# TIDA-010954-FullBridge.net
KiCad netlist of a schematic drawn in Altium Designer
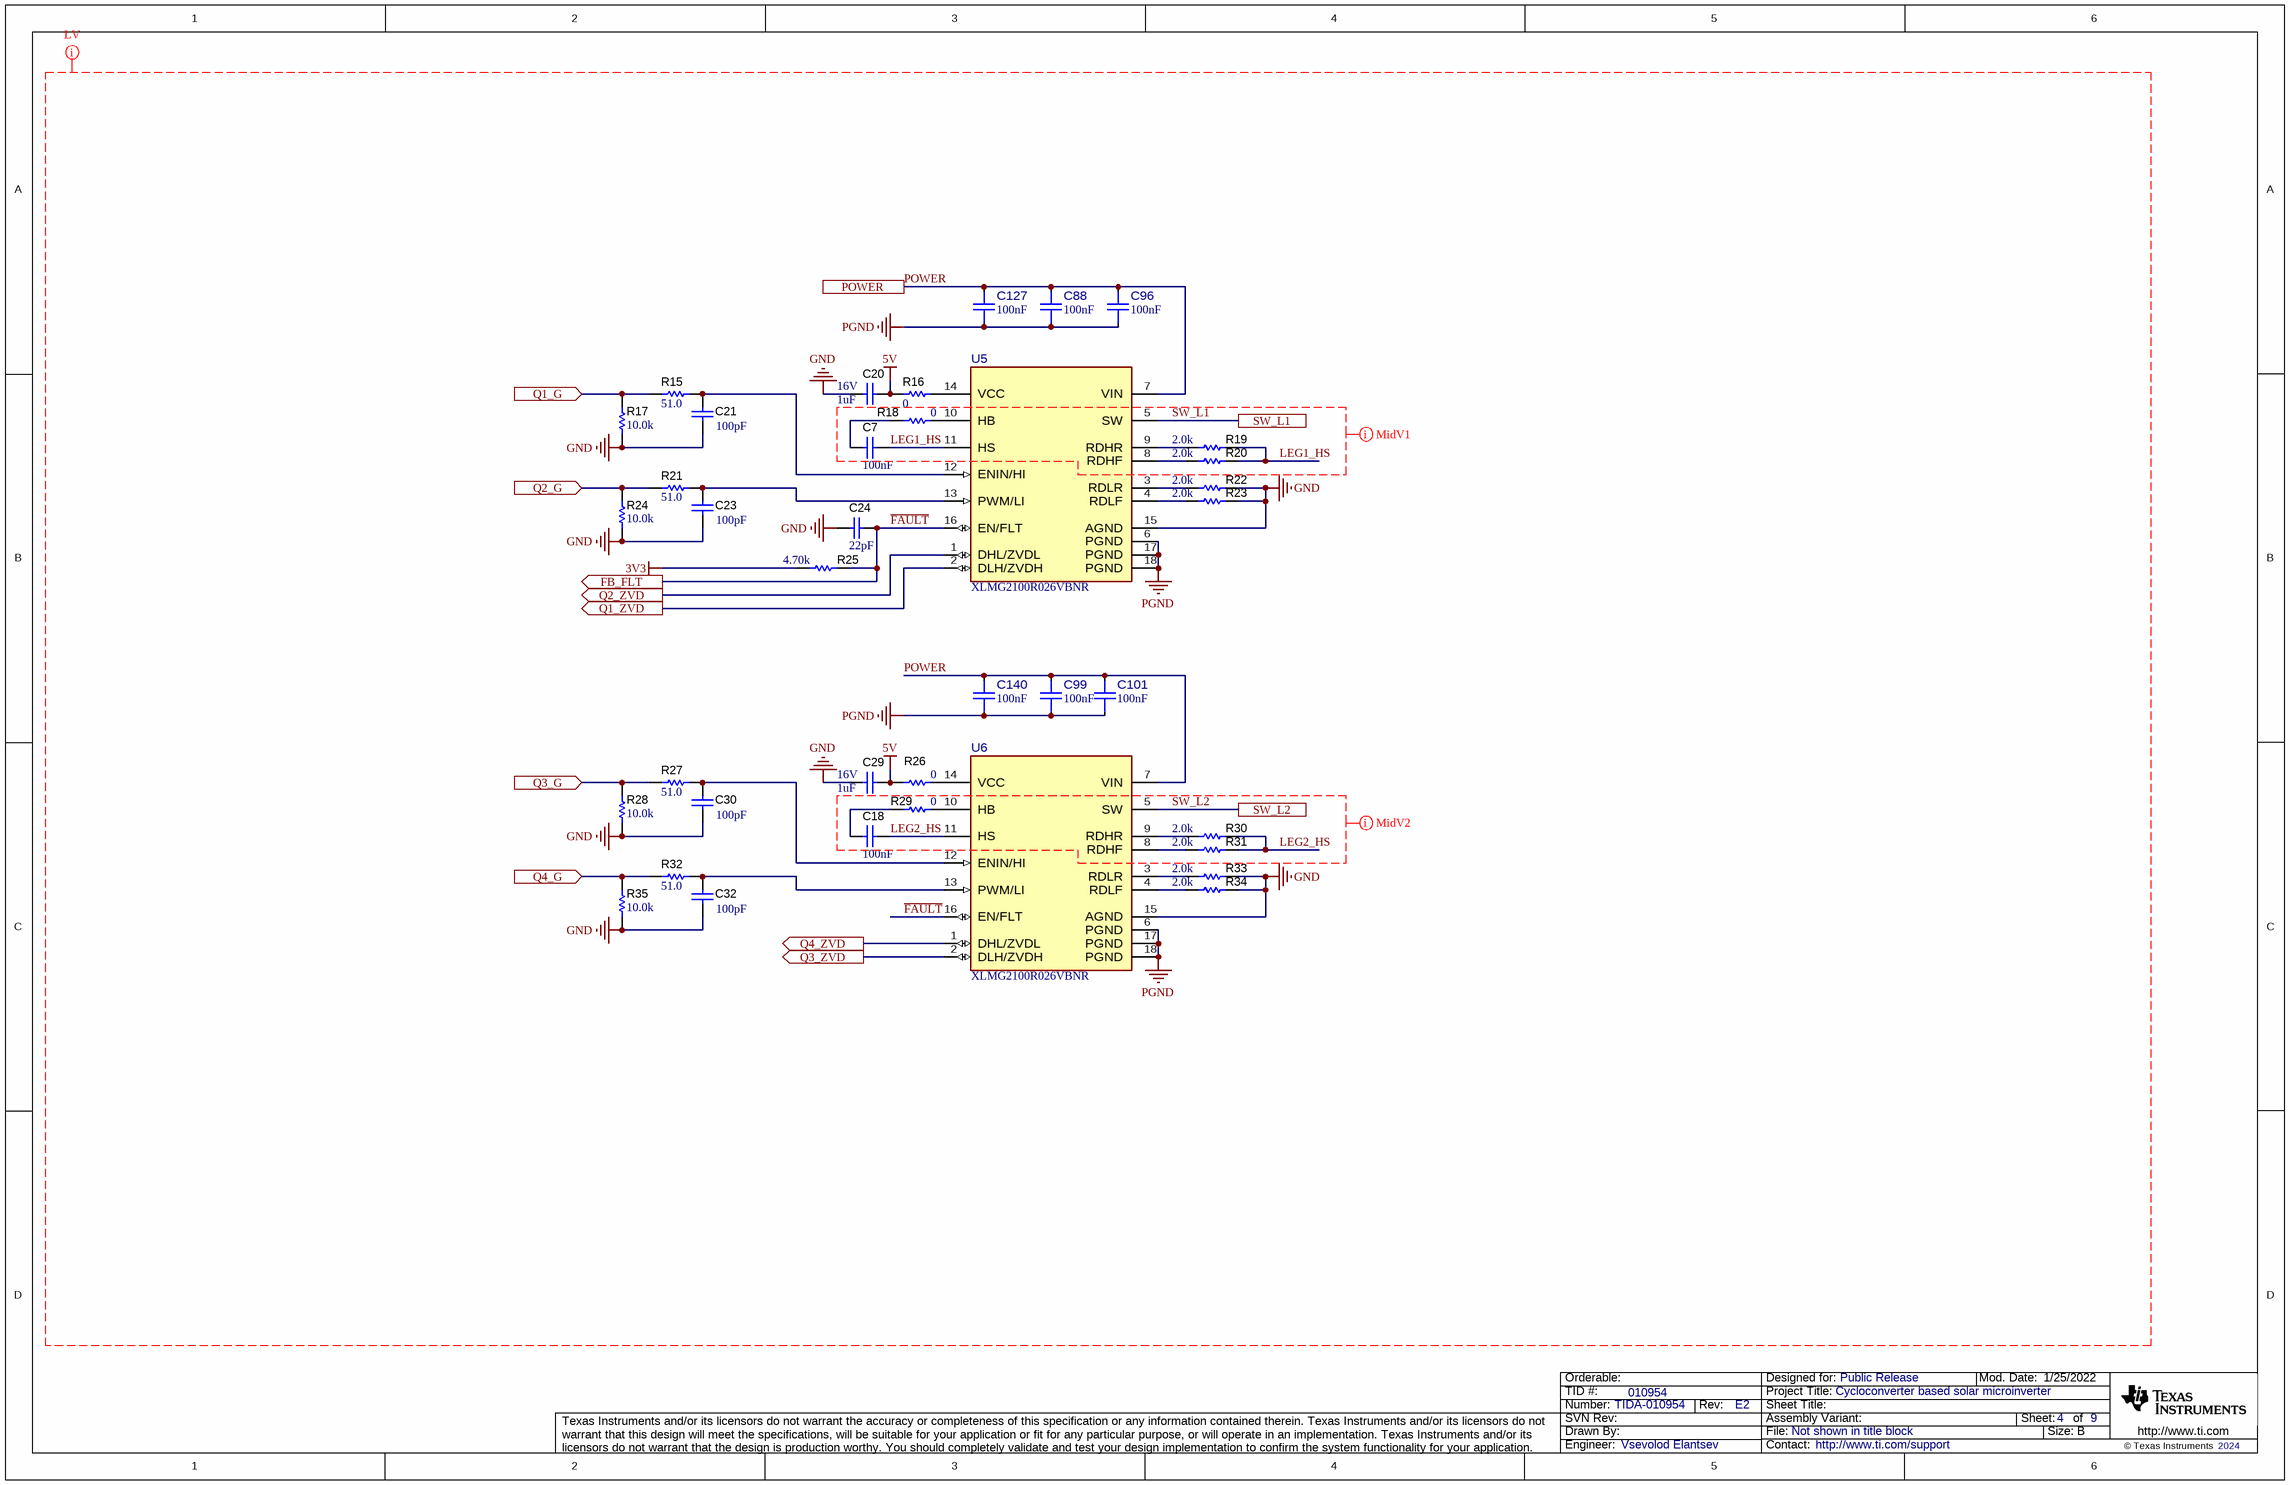
[diagram p0: TIDA-010954-FullBridge.SchDoc]

(export (version "E")
  (design (tool "Eeschema 10.0.6"))
  (components
    (comp (ref "C7")
      (value "CGA3E2X7R1E104K080AA")
      (footprint "0603")
      (description "CAP, CERM, 0.1 uF, 25 V, +/- 10%, X7R, AEC-Q200 Grade 1, 0603")
      (fields
        (field (name "MANUFACTURER") "TDK")
        (field (name "CAP_F") "100nF")
        (field (name "PUBLISHER") "Texas Instruments")
      )
      (libsource (lib "Altium Vault - TI") (part "Capacitor"))
    )
    (comp (ref "C18")
      (value "CGA3E2X7R1E104K080AA")
      (footprint "0603")
      (description "CAP, CERM, 0.1 uF, 25 V, +/- 10%, X7R, AEC-Q200 Grade 1, 0603")
      (fields
        (field (name "MANUFACTURER") "TDK")
        (field (name "CAP_F") "100nF")
        (field (name "PUBLISHER") "Texas Instruments")
      )
      (libsource (lib "Altium Vault - TI") (part "Capacitor"))
    )
    (comp (ref "C20")
      (value "GRM185R61C105KE44D")
      (footprint "0603")
      (description "CAP, CERM, 1 uF, 16 V, +/- 10%, X5R, 0603")
      (fields
        (field (name "MANUFACTURER") "MuRata")
        (field (name "VDC_V") "16V")
        (field (name "VALUEDISPLAYED") "1uF")
        (field (name "PUBLISHER") "Texas Instruments")
      )
      (libsource (lib "Altium Vault - TI") (part "Capacitor"))
    )
    (comp (ref "C21")
      (value "GRM1885C1H101JA01D")
      (footprint "0603")
      (description "CAP, CERM, 100 pF, 50 V, +/- 5%, C0G/NP0, 0603")
      (fields
        (field (name "MANUFACTURER") "MuRata")
        (field (name "VALUEDISPLAYED") "100pF")
        (field (name "PUBLISHER") "Texas Instruments")
      )
      (libsource (lib "Altium Vault - TI") (part "Capacitor"))
    )
    (comp (ref "C23")
      (value "GRM1885C1H101JA01D")
      (footprint "0603")
      (description "CAP, CERM, 100 pF, 50 V, +/- 5%, C0G/NP0, 0603")
      (fields
        (field (name "MANUFACTURER") "MuRata")
        (field (name "VALUEDISPLAYED") "100pF")
        (field (name "PUBLISHER") "Texas Instruments")
      )
      (libsource (lib "Altium Vault - TI") (part "Capacitor"))
    )
    (comp (ref "C24")
      (value "GRM1885C1H220JA01D")
      (footprint "0603")
      (description "CAP, CERM, 22 pF, 50 V, +/- 5%, C0G/NP0, 0603")
      (fields
        (field (name "MANUFACTURER") "MuRata")
        (field (name "VALUEDISPLAYED") "22pF")
        (field (name "PUBLISHER") "Texas Instruments")
      )
      (libsource (lib "Altium Vault - TI") (part "Capacitor"))
    )
    (comp (ref "C29")
      (value "GRM185R61C105KE44D")
      (footprint "0603")
      (description "CAP, CERM, 1 uF, 16 V, +/- 10%, X5R, 0603")
      (fields
        (field (name "MANUFACTURER") "MuRata")
        (field (name "VDC_V") "16V")
        (field (name "VALUEDISPLAYED") "1uF")
        (field (name "PUBLISHER") "Texas Instruments")
      )
      (libsource (lib "Altium Vault - TI") (part "Capacitor"))
    )
    (comp (ref "C30")
      (value "GRM1885C1H101JA01D")
      (footprint "0603")
      (description "CAP, CERM, 100 pF, 50 V, +/- 5%, C0G/NP0, 0603")
      (fields
        (field (name "MANUFACTURER") "MuRata")
        (field (name "VALUEDISPLAYED") "100pF")
        (field (name "PUBLISHER") "Texas Instruments")
      )
      (libsource (lib "Altium Vault - TI") (part "Capacitor"))
    )
    (comp (ref "C32")
      (value "GRM1885C1H101JA01D")
      (footprint "0603")
      (description "CAP, CERM, 100 pF, 50 V, +/- 5%, C0G/NP0, 0603")
      (fields
        (field (name "MANUFACTURER") "MuRata")
        (field (name "VALUEDISPLAYED") "100pF")
        (field (name "PUBLISHER") "Texas Instruments")
      )
      (libsource (lib "Altium Vault - TI") (part "Capacitor"))
    )
    (comp (ref "C88")
      (value "GRM188R72A104KA35J")
      (footprint "FP-GRM188R72A104KA35J_0603-MFG")
      (description "Chip Multilayer Ceramic Capacitors for General Purpose, 0603, 0.10uF, X7R, 15%, 10%, 100V")
      (fields (field (name "CAP_F") "100nF") (field (name "MANUFACTURER") "Murata"))
      (libsource (lib "Altium Vault - TI") (part "SYM-GRM188R72A104KA35J"))
    )
    (comp (ref "C96")
      (value "GRM188R72A104KA35J")
      (footprint "FP-GRM188R72A104KA35J_0603-MFG")
      (description "Chip Multilayer Ceramic Capacitors for General Purpose, 0603, 0.10uF, X7R, 15%, 10%, 100V")
      (fields (field (name "CAP_F") "100nF") (field (name "MANUFACTURER") "Murata"))
      (libsource (lib "Altium Vault - TI") (part "SYM-GRM188R72A104KA35J"))
    )
    (comp (ref "C99")
      (value "GRM188R72A104KA35J")
      (footprint "FP-GRM188R72A104KA35J_0603-MFG")
      (description "Chip Multilayer Ceramic Capacitors for General Purpose, 0603, 0.10uF, X7R, 15%, 10%, 100V")
      (fields (field (name "CAP_F") "100nF") (field (name "MANUFACTURER") "Murata"))
      (libsource (lib "Altium Vault - TI") (part "SYM-GRM188R72A104KA35J"))
    )
    (comp (ref "C101")
      (value "GRM188R72A104KA35J")
      (footprint "FP-GRM188R72A104KA35J_0603-MFG")
      (description "Chip Multilayer Ceramic Capacitors for General Purpose, 0603, 0.10uF, X7R, 15%, 10%, 100V")
      (fields (field (name "CAP_F") "100nF") (field (name "MANUFACTURER") "Murata"))
      (libsource (lib "Altium Vault - TI") (part "SYM-GRM188R72A104KA35J"))
    )
    (comp (ref "C127")
      (value "GRM188R72A104KA35J")
      (footprint "FP-GRM188R72A104KA35J_0603-MFG")
      (description "Chip Multilayer Ceramic Capacitors for General Purpose, 0603, 0.10uF, X7R, 15%, 10%, 100V")
      (fields (field (name "CAP_F") "100nF") (field (name "MANUFACTURER") "Murata"))
      (libsource (lib "Altium Vault - TI") (part "SYM-GRM188R72A104KA35J"))
    )
    (comp (ref "C140")
      (value "GRM188R72A104KA35J")
      (footprint "FP-GRM188R72A104KA35J_0603-MFG")
      (description "Chip Multilayer Ceramic Capacitors for General Purpose, 0603, 0.10uF, X7R, 15%, 10%, 100V")
      (fields (field (name "CAP_F") "100nF") (field (name "MANUFACTURER") "Murata"))
      (libsource (lib "Altium Vault - TI") (part "SYM-GRM188R72A104KA35J"))
    )
    (comp (ref "R15")
      (value "RC0603FR-0751RL")
      (footprint "0603")
      (description "RES, 51.0, 1%, 0.1 W, 0603")
      (fields (field (name "MANUFACTURER") "Yageo") (field (name "VALUEDISPLAYED") "51.0"))
      (libsource (lib "Altium Vault - TI") (part "Resistor"))
    )
    (comp (ref "R16")
      (value "RC0603JR-070RL")
      (footprint "0603")
      (description "RES, 0, 5%, 0.1 W, 0603")
      (fields (field (name "MANUFACTURER") "Yageo") (field (name "VALUEDISPLAYED") "0"))
      (libsource (lib "Altium Vault - TI") (part "Resistor"))
    )
    (comp (ref "R17")
      (value "RC0603FR-0710KL")
      (footprint "0603")
      (description "RES, 10.0 k, 1%, 0.1 W, 0603")
      (fields (field (name "MANUFACTURER") "Yageo") (field (name "VALUEDISPLAYED") "10.0k"))
      (libsource (lib "Altium Vault - TI") (part "Resistor"))
    )
    (comp (ref "R18")
      (value "RC0603JR-070RL")
      (footprint "0603")
      (description "RES, 0, 5%, 0.1 W, 0603")
      (fields (field (name "MANUFACTURER") "Yageo") (field (name "VALUEDISPLAYED") "0"))
      (libsource (lib "Altium Vault - TI") (part "Resistor"))
    )
    (comp (ref "R19")
      (value "RC0603JR-072KL")
      (footprint "0603")
      (description "RES, 2.0 k, 5%, 0.1 W, 0603")
      (fields (field (name "MANUFACTURER") "Yageo") (field (name "VALUEDISPLAYED") "2.0k"))
      (libsource (lib "Altium Vault - TI") (part "Resistor"))
    )
    (comp (ref "R20")
      (value "RC0603JR-072KL")
      (footprint "0603")
      (description "RES, 2.0 k, 5%, 0.1 W, 0603")
      (fields (field (name "MANUFACTURER") "Yageo") (field (name "VALUEDISPLAYED") "2.0k"))
      (libsource (lib "Altium Vault - TI") (part "Resistor"))
    )
    (comp (ref "R21")
      (value "RC0603FR-0751RL")
      (footprint "0603")
      (description "RES, 51.0, 1%, 0.1 W, 0603")
      (fields (field (name "MANUFACTURER") "Yageo") (field (name "VALUEDISPLAYED") "51.0"))
      (libsource (lib "Altium Vault - TI") (part "Resistor"))
    )
    (comp (ref "R22")
      (value "RC0603JR-072KL")
      (footprint "0603")
      (description "RES, 2.0 k, 5%, 0.1 W, 0603")
      (fields (field (name "MANUFACTURER") "Yageo") (field (name "VALUEDISPLAYED") "2.0k"))
      (libsource (lib "Altium Vault - TI") (part "Resistor"))
    )
    (comp (ref "R23")
      (value "RC0603JR-072KL")
      (footprint "0603")
      (description "RES, 2.0 k, 5%, 0.1 W, 0603")
      (fields (field (name "MANUFACTURER") "Yageo") (field (name "VALUEDISPLAYED") "2.0k"))
      (libsource (lib "Altium Vault - TI") (part "Resistor"))
    )
    (comp (ref "R24")
      (value "RC0603FR-0710KL")
      (footprint "0603")
      (description "RES, 10.0 k, 1%, 0.1 W, 0603")
      (fields (field (name "MANUFACTURER") "Yageo") (field (name "VALUEDISPLAYED") "10.0k"))
      (libsource (lib "Altium Vault - TI") (part "Resistor"))
    )
    (comp (ref "R25")
      (value "RC0603FR-074K7L")
      (footprint "0603")
      (description "RES, 4.70 k, 1%, 0.1 W, 0603")
      (fields (field (name "MANUFACTURER") "Yageo") (field (name "VALUEDISPLAYED") "4.70k"))
      (libsource (lib "Altium Vault - TI") (part "Resistor"))
    )
    (comp (ref "R26")
      (value "RC0603JR-070RL")
      (footprint "0603")
      (description "RES, 0, 5%, 0.1 W, 0603")
      (fields (field (name "MANUFACTURER") "Yageo") (field (name "VALUEDISPLAYED") "0"))
      (libsource (lib "Altium Vault - TI") (part "Resistor"))
    )
    (comp (ref "R27")
      (value "RC0603FR-0751RL")
      (footprint "0603")
      (description "RES, 51.0, 1%, 0.1 W, 0603")
      (fields (field (name "MANUFACTURER") "Yageo") (field (name "VALUEDISPLAYED") "51.0"))
      (libsource (lib "Altium Vault - TI") (part "Resistor"))
    )
    (comp (ref "R28")
      (value "RC0603FR-0710KL")
      (footprint "0603")
      (description "RES, 10.0 k, 1%, 0.1 W, 0603")
      (fields (field (name "MANUFACTURER") "Yageo") (field (name "VALUEDISPLAYED") "10.0k"))
      (libsource (lib "Altium Vault - TI") (part "Resistor"))
    )
    (comp (ref "R29")
      (value "RC0603JR-070RL")
      (footprint "0603")
      (description "RES, 0, 5%, 0.1 W, 0603")
      (fields (field (name "MANUFACTURER") "Yageo") (field (name "VALUEDISPLAYED") "0"))
      (libsource (lib "Altium Vault - TI") (part "Resistor"))
    )
    (comp (ref "R30")
      (value "RC0603JR-072KL")
      (footprint "0603")
      (description "RES, 2.0 k, 5%, 0.1 W, 0603")
      (fields (field (name "MANUFACTURER") "Yageo") (field (name "VALUEDISPLAYED") "2.0k"))
      (libsource (lib "Altium Vault - TI") (part "Resistor"))
    )
    (comp (ref "R31")
      (value "RC0603JR-072KL")
      (footprint "0603")
      (description "RES, 2.0 k, 5%, 0.1 W, 0603")
      (fields (field (name "MANUFACTURER") "Yageo") (field (name "VALUEDISPLAYED") "2.0k"))
      (libsource (lib "Altium Vault - TI") (part "Resistor"))
    )
    (comp (ref "R32")
      (value "RC0603FR-0751RL")
      (footprint "0603")
      (description "RES, 51.0, 1%, 0.1 W, 0603")
      (fields (field (name "MANUFACTURER") "Yageo") (field (name "VALUEDISPLAYED") "51.0"))
      (libsource (lib "Altium Vault - TI") (part "Resistor"))
    )
    (comp (ref "R33")
      (value "RC0603JR-072KL")
      (footprint "0603")
      (description "RES, 2.0 k, 5%, 0.1 W, 0603")
      (fields (field (name "MANUFACTURER") "Yageo") (field (name "VALUEDISPLAYED") "2.0k"))
      (libsource (lib "Altium Vault - TI") (part "Resistor"))
    )
    (comp (ref "R34")
      (value "RC0603JR-072KL")
      (footprint "0603")
      (description "RES, 2.0 k, 5%, 0.1 W, 0603")
      (fields (field (name "MANUFACTURER") "Yageo") (field (name "VALUEDISPLAYED") "2.0k"))
      (libsource (lib "Altium Vault - TI") (part "Resistor"))
    )
    (comp (ref "R35")
      (value "RC0603FR-0710KL")
      (footprint "0603")
      (description "RES, 10.0 k, 1%, 0.1 W, 0603")
      (fields (field (name "MANUFACTURER") "Yageo") (field (name "VALUEDISPLAYED") "10.0k"))
      (libsource (lib "Altium Vault - TI") (part "Resistor"))
    )
    (comp (ref "U5")
      (value "XLMG2100R026VBNR")
      (footprint "VBN0018A-MFG")
      (description "170-V GaN Half-Bridge Power Stages")
      (fields
        (field (name "MANUFACTURER") "Texas Instruments")
        (field (name "PARTNUMBER") "XLMG2100R026VBNR")
        (field (name "PART NUMBER") "LMG2175")
      )
      (libsource (lib "Altium Vault - TI") (part "SYM-LMG2175"))
    )
    (comp (ref "U6")
      (value "XLMG2100R026VBNR")
      (footprint "VBN0018A-MFG")
      (description "170-V GaN Half-Bridge Power Stages")
      (fields
        (field (name "MANUFACTURER") "Texas Instruments")
        (field (name "PARTNUMBER") "XLMG2100R026VBNR")
        (field (name "PART NUMBER") "LMG2175")
      )
      (libsource (lib "Altium Vault - TI") (part "SYM-LMG2175"))
    )
  )
  (nets
    (net (code "1") (name "/LEG1_HS") (class "Default")
      (node (ref "C7") (pin "2") (pinfunction "2_2") (pintype "passive"))
      (node (ref "R19") (pin "2") (pinfunction "2_2") (pintype "passive"))
      (node (ref "R20") (pin "2") (pinfunction "2_2") (pintype "passive"))
      (node (ref "U5") (pin "11") (pinfunction "HS_11") (pintype "power_in"))
    )
    (net (code "2") (name "/LEG2_HS") (class "Default")
      (node (ref "C18") (pin "2") (pinfunction "2_2") (pintype "passive"))
      (node (ref "R30") (pin "2") (pinfunction "2_2") (pintype "passive"))
      (node (ref "R31") (pin "2") (pinfunction "2_2") (pintype "passive"))
      (node (ref "U6") (pin "11") (pinfunction "HS_11") (pintype "power_in"))
    )
    (net (code "3") (name "/POWER") (class "Default")
      (node (ref "C101") (pin "2") (pinfunction "2_2") (pintype "passive"))
      (node (ref "C127") (pin "2") (pinfunction "2_2") (pintype "passive"))
      (node (ref "C140") (pin "2") (pinfunction "2_2") (pintype "passive"))
      (node (ref "C88") (pin "2") (pinfunction "2_2") (pintype "passive"))
      (node (ref "C96") (pin "2") (pinfunction "2_2") (pintype "passive"))
      (node (ref "C99") (pin "2") (pinfunction "2_2") (pintype "passive"))
      (node (ref "U5") (pin "7") (pinfunction "VIN_7") (pintype "power_in"))
      (node (ref "U6") (pin "7") (pinfunction "VIN_7") (pintype "power_in"))
    )
    (net (code "4") (name "/Q1_G") (class "Default")
      (node (ref "R15") (pin "1") (pinfunction "1_1") (pintype "passive"))
      (node (ref "R17") (pin "2") (pinfunction "2_2") (pintype "passive"))
    )
    (net (code "5") (name "/Q1_ZVD") (class "Default")
      (node (ref "U5") (pin "2") (pinfunction "DLH/ZVDH_2") (pintype "bidirectional"))
    )
    (net (code "6") (name "/Q2_G") (class "Default")
      (node (ref "R21") (pin "1") (pinfunction "1_1") (pintype "passive"))
      (node (ref "R24") (pin "2") (pinfunction "2_2") (pintype "passive"))
    )
    (net (code "7") (name "/Q2_ZVD") (class "Default")
      (node (ref "U5") (pin "1") (pinfunction "DHL/ZVDL_1") (pintype "bidirectional"))
    )
    (net (code "8") (name "/Q3_G") (class "Default")
      (node (ref "R27") (pin "1") (pinfunction "1_1") (pintype "passive"))
      (node (ref "R28") (pin "2") (pinfunction "2_2") (pintype "passive"))
    )
    (net (code "9") (name "/Q3_ZVD") (class "Default")
      (node (ref "U6") (pin "2") (pinfunction "DLH/ZVDH_2") (pintype "bidirectional"))
    )
    (net (code "10") (name "/Q4_G") (class "Default")
      (node (ref "R32") (pin "1") (pinfunction "1_1") (pintype "passive"))
      (node (ref "R35") (pin "2") (pinfunction "2_2") (pintype "passive"))
    )
    (net (code "11") (name "/Q4_ZVD") (class "Default")
      (node (ref "U6") (pin "1") (pinfunction "DHL/ZVDL_1") (pintype "bidirectional"))
    )
    (net (code "12") (name "/SW_L1") (class "Default")
      (node (ref "U5") (pin "5") (pinfunction "SW_5") (pintype "power_in"))
    )
    (net (code "13") (name "/SW_L2") (class "Default")
      (node (ref "U6") (pin "5") (pinfunction "SW_5") (pintype "power_in"))
    )
    (net (code "14") (name "/~{FAULT}") (class "Default")
      (node (ref "C24") (pin "2") (pinfunction "2_2") (pintype "passive"))
      (node (ref "R25") (pin "2") (pinfunction "2_2") (pintype "passive"))
      (node (ref "U5") (pin "16") (pinfunction "EN/FLT_16") (pintype "bidirectional"))
      (node (ref "U6") (pin "16") (pinfunction "EN/FLT_16") (pintype "bidirectional"))
    )
    (net (code "15") (name "3V3") (class "Default")
      (node (ref "R25") (pin "1") (pinfunction "1_1") (pintype "passive"))
    )
    (net (code "16") (name "5V") (class "Default")
      (node (ref "C20") (pin "2") (pinfunction "2_2") (pintype "passive"))
      (node (ref "C29") (pin "2") (pinfunction "2_2") (pintype "passive"))
      (node (ref "R16") (pin "1") (pinfunction "1_1") (pintype "passive"))
      (node (ref "R26") (pin "1") (pinfunction "1_1") (pintype "passive"))
    )
    (net (code "17") (name "GND") (class "Default")
      (node (ref "C20") (pin "1") (pinfunction "1_1") (pintype "passive"))
      (node (ref "C21") (pin "2") (pinfunction "2_2") (pintype "passive"))
      (node (ref "C23") (pin "2") (pinfunction "2_2") (pintype "passive"))
      (node (ref "C24") (pin "1") (pinfunction "1_1") (pintype "passive"))
      (node (ref "C29") (pin "1") (pinfunction "1_1") (pintype "passive"))
      (node (ref "C30") (pin "2") (pinfunction "2_2") (pintype "passive"))
      (node (ref "C32") (pin "2") (pinfunction "2_2") (pintype "passive"))
      (node (ref "R17") (pin "1") (pinfunction "1_1") (pintype "passive"))
      (node (ref "R22") (pin "2") (pinfunction "2_2") (pintype "passive"))
      (node (ref "R23") (pin "2") (pinfunction "2_2") (pintype "passive"))
      (node (ref "R24") (pin "1") (pinfunction "1_1") (pintype "passive"))
      (node (ref "R28") (pin "1") (pinfunction "1_1") (pintype "passive"))
      (node (ref "R33") (pin "2") (pinfunction "2_2") (pintype "passive"))
      (node (ref "R34") (pin "2") (pinfunction "2_2") (pintype "passive"))
      (node (ref "R35") (pin "1") (pinfunction "1_1") (pintype "passive"))
      (node (ref "U5") (pin "15") (pinfunction "AGND_15") (pintype "power_in"))
      (node (ref "U6") (pin "15") (pinfunction "AGND_15") (pintype "power_in"))
    )
    (net (code "18") (name "Net-(C7-Pad1)") (class "Default")
      (node (ref "C7") (pin "1") (pinfunction "1_1") (pintype "passive"))
      (node (ref "R18") (pin "1") (pinfunction "1_1") (pintype "passive"))
    )
    (net (code "19") (name "Net-(C18-Pad1)") (class "Default")
      (node (ref "C18") (pin "1") (pinfunction "1_1") (pintype "passive"))
      (node (ref "R29") (pin "1") (pinfunction "1_1") (pintype "passive"))
    )
    (net (code "20") (name "Net-(U5-ENIN{slash}HI)") (class "Default")
      (node (ref "C21") (pin "1") (pinfunction "1_1") (pintype "passive"))
      (node (ref "R15") (pin "2") (pinfunction "2_2") (pintype "passive"))
      (node (ref "U5") (pin "12") (pinfunction "ENIN/HI_12") (pintype "input"))
    )
    (net (code "21") (name "Net-(U5-HB)") (class "Default")
      (node (ref "R18") (pin "2") (pinfunction "2_2") (pintype "passive"))
      (node (ref "U5") (pin "10") (pinfunction "HB_10") (pintype "power_in"))
    )
    (net (code "22") (name "Net-(U5-PWM{slash}LI)") (class "Default")
      (node (ref "C23") (pin "1") (pinfunction "1_1") (pintype "passive"))
      (node (ref "R21") (pin "2") (pinfunction "2_2") (pintype "passive"))
      (node (ref "U5") (pin "13") (pinfunction "PWM/LI_13") (pintype "input"))
    )
    (net (code "23") (name "Net-(U5-RDHF)") (class "Default")
      (node (ref "R20") (pin "1") (pinfunction "1_1") (pintype "passive"))
      (node (ref "U5") (pin "8") (pinfunction "RDHF_8") (pintype "passive"))
    )
    (net (code "24") (name "Net-(U5-RDHR)") (class "Default")
      (node (ref "R19") (pin "1") (pinfunction "1_1") (pintype "passive"))
      (node (ref "U5") (pin "9") (pinfunction "RDHR_9") (pintype "passive"))
    )
    (net (code "25") (name "Net-(U5-RDLF)") (class "Default")
      (node (ref "R23") (pin "1") (pinfunction "1_1") (pintype "passive"))
      (node (ref "U5") (pin "4") (pinfunction "RDLF_4") (pintype "passive"))
    )
    (net (code "26") (name "Net-(U5-RDLR)") (class "Default")
      (node (ref "R22") (pin "1") (pinfunction "1_1") (pintype "passive"))
      (node (ref "U5") (pin "3") (pinfunction "RDLR_3") (pintype "passive"))
    )
    (net (code "27") (name "Net-(U5-VCC)") (class "Default")
      (node (ref "R16") (pin "2") (pinfunction "2_2") (pintype "passive"))
      (node (ref "U5") (pin "14") (pinfunction "VCC_14") (pintype "power_in"))
    )
    (net (code "28") (name "Net-(U6-ENIN{slash}HI)") (class "Default")
      (node (ref "C30") (pin "1") (pinfunction "1_1") (pintype "passive"))
      (node (ref "R27") (pin "2") (pinfunction "2_2") (pintype "passive"))
      (node (ref "U6") (pin "12") (pinfunction "ENIN/HI_12") (pintype "input"))
    )
    (net (code "29") (name "Net-(U6-HB)") (class "Default")
      (node (ref "R29") (pin "2") (pinfunction "2_2") (pintype "passive"))
      (node (ref "U6") (pin "10") (pinfunction "HB_10") (pintype "power_in"))
    )
    (net (code "30") (name "Net-(U6-PWM{slash}LI)") (class "Default")
      (node (ref "C32") (pin "1") (pinfunction "1_1") (pintype "passive"))
      (node (ref "R32") (pin "2") (pinfunction "2_2") (pintype "passive"))
      (node (ref "U6") (pin "13") (pinfunction "PWM/LI_13") (pintype "input"))
    )
    (net (code "31") (name "Net-(U6-RDHF)") (class "Default")
      (node (ref "R31") (pin "1") (pinfunction "1_1") (pintype "passive"))
      (node (ref "U6") (pin "8") (pinfunction "RDHF_8") (pintype "passive"))
    )
    (net (code "32") (name "Net-(U6-RDHR)") (class "Default")
      (node (ref "R30") (pin "1") (pinfunction "1_1") (pintype "passive"))
      (node (ref "U6") (pin "9") (pinfunction "RDHR_9") (pintype "passive"))
    )
    (net (code "33") (name "Net-(U6-RDLF)") (class "Default")
      (node (ref "R34") (pin "1") (pinfunction "1_1") (pintype "passive"))
      (node (ref "U6") (pin "4") (pinfunction "RDLF_4") (pintype "passive"))
    )
    (net (code "34") (name "Net-(U6-RDLR)") (class "Default")
      (node (ref "R33") (pin "1") (pinfunction "1_1") (pintype "passive"))
      (node (ref "U6") (pin "3") (pinfunction "RDLR_3") (pintype "passive"))
    )
    (net (code "35") (name "Net-(U6-VCC)") (class "Default")
      (node (ref "R26") (pin "2") (pinfunction "2_2") (pintype "passive"))
      (node (ref "U6") (pin "14") (pinfunction "VCC_14") (pintype "power_in"))
    )
    (net (code "36") (name "PGND") (class "Default")
      (node (ref "C101") (pin "1") (pinfunction "1_1") (pintype "passive"))
      (node (ref "C127") (pin "1") (pinfunction "1_1") (pintype "passive"))
      (node (ref "C140") (pin "1") (pinfunction "1_1") (pintype "passive"))
      (node (ref "C88") (pin "1") (pinfunction "1_1") (pintype "passive"))
      (node (ref "C96") (pin "1") (pinfunction "1_1") (pintype "passive"))
      (node (ref "C99") (pin "1") (pinfunction "1_1") (pintype "passive"))
      (node (ref "U5") (pin "17") (pinfunction "PGND_17") (pintype "power_in"))
      (node (ref "U5") (pin "18") (pinfunction "PGND_18") (pintype "power_in"))
      (node (ref "U5") (pin "6") (pinfunction "PGND_6") (pintype "power_in"))
      (node (ref "U6") (pin "17") (pinfunction "PGND_17") (pintype "power_in"))
      (node (ref "U6") (pin "18") (pinfunction "PGND_18") (pintype "power_in"))
      (node (ref "U6") (pin "6") (pinfunction "PGND_6") (pintype "power_in"))
    )
  )
)
